# Driver_Morpheus_v4_0_PONTE_H.net
KiCad netlist of a schematic drawn in Altium Designer
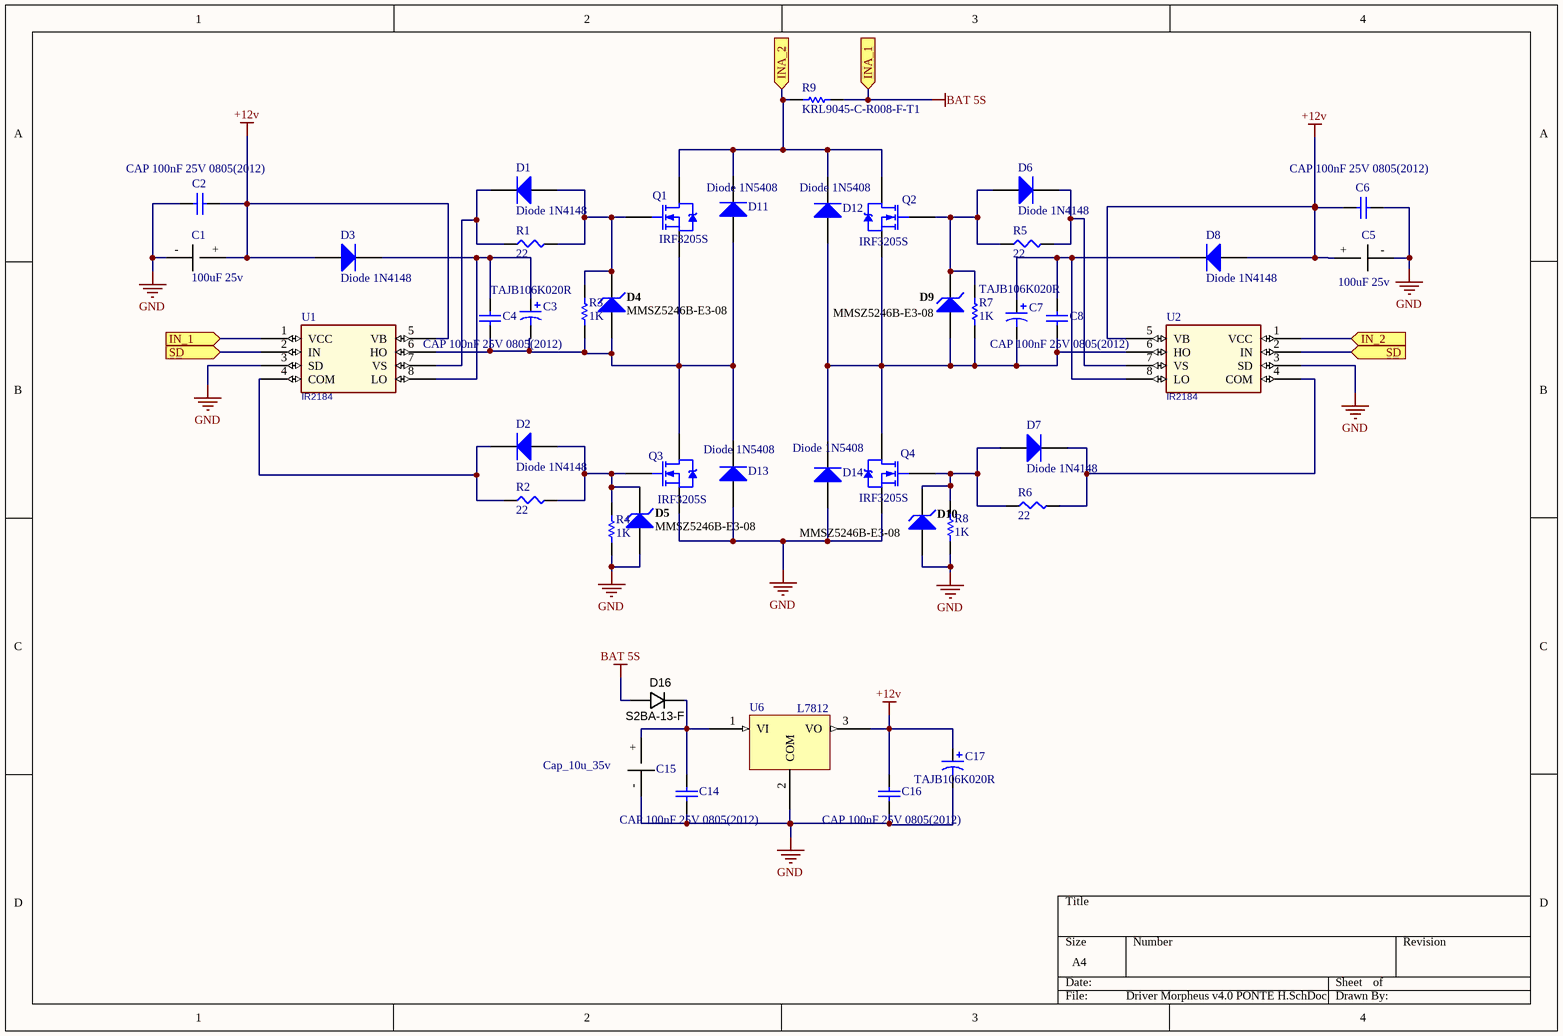
[diagram p0: Driver Morpheus v4.0 PONTE H.SchDoc]

(export (version "E")
  (design (tool "Eeschema 10.0.6"))
  (components
    (comp (ref "C1")
      (value "100uF 25v")
      (footprint "CAP_100u_25v_Tantalum")
      (description "Cap Tântalo")
      (libsource (lib "LibSanhaço2017") (part "Cap_100u_25v"))
    )
    (comp (ref "C2")
      (value "CAP 100nF 25V 0805(2012)")
      (footprint "CAPC0805(2012)145_M")
      (description "CAP 100nF 25V ±5% 0805 (2012 Metric) Thickness 1.45mm SMD")
      (fields (field (name "TOLERANCE") "Â±5%"))
      (libsource (lib "Altium Content Vault") (part "CAP"))
    )
    (comp (ref "C3")
      (value "TAJB106K020R")
      (footprint "AVX-CAPC3528_V")
      (description "Capacitor, Tantalum, 10uF 10% 20V MCCT-B (3528)")
      (fields (field (name "MANUFACTURER") "AVX") (field (name "TOLERANCE") "10%"))
      (libsource (lib "Altium Content Vault") (part "AVX-CAP-P-2"))
    )
    (comp (ref "C4")
      (value "CAP 100nF 25V 0805(2012)")
      (footprint "CAPC0805(2012)145_M")
      (description "CAP 100nF 25V ±5% 0805 (2012 Metric) Thickness 1.45mm SMD")
      (fields (field (name "TOLERANCE") "Â±5%"))
      (libsource (lib "Altium Content Vault") (part "CAP"))
    )
    (comp (ref "C5")
      (value "100uF 25v")
      (footprint "CAP_100u_25v_Tantalum")
      (description "Cap Tântalo")
      (libsource (lib "LibSanhaço2017") (part "Cap_100u_25v"))
    )
    (comp (ref "C6")
      (value "CAP 100nF 25V 0805(2012)")
      (footprint "CAPC0805(2012)145_M")
      (description "CAP 100nF 25V ±5% 0805 (2012 Metric) Thickness 1.45mm SMD")
      (fields (field (name "TOLERANCE") "Â±5%"))
      (libsource (lib "Altium Content Vault") (part "CAP"))
    )
    (comp (ref "C7")
      (value "TAJB106K020R")
      (footprint "AVX-CAPC3528_V")
      (description "Capacitor, Tantalum, 10uF 10% 20V MCCT-B (3528)")
      (fields (field (name "MANUFACTURER") "AVX") (field (name "TOLERANCE") "10%"))
      (libsource (lib "Altium Content Vault") (part "AVX-CAP-P-2"))
    )
    (comp (ref "C8")
      (value "CAP 100nF 25V 0805(2012)")
      (footprint "CAPC0805(2012)145_M")
      (description "CAP 100nF 25V ±5% 0805 (2012 Metric) Thickness 1.45mm SMD")
      (fields (field (name "TOLERANCE") "Â±5%"))
      (libsource (lib "Altium Content Vault") (part "CAP"))
    )
    (comp (ref "C14")
      (value "CAP 100nF 25V 0805(2012)")
      (footprint "CAPC0805(2012)145_M")
      (description "CAP 100nF 25V ±5% 0805 (2012 Metric) Thickness 1.45mm SMD")
      (fields (field (name "TOLERANCE") "Â±5%"))
      (libsource (lib "Altium Content Vault") (part "CAP"))
    )
    (comp (ref "C15")
      (value "Cap_10u_35v")
      (footprint "CAP_100u_25v_Tantalum")
      (libsource (lib "LibSanhaço2017") (part "Cap_10u_35v"))
    )
    (comp (ref "C16")
      (value "CAP 100nF 25V 0805(2012)")
      (footprint "CAPC0805(2012)145_M")
      (description "CAP 100nF 25V ±5% 0805 (2012 Metric) Thickness 1.45mm SMD")
      (fields (field (name "TOLERANCE") "Â±5%"))
      (libsource (lib "Altium Content Vault") (part "CAP"))
    )
    (comp (ref "C17")
      (value "TAJB106K020R")
      (footprint "AVX-CAPC3528_V")
      (description "Capacitor, Tantalum, 10uF 10% 20V MCCT-B (3528)")
      (fields (field (name "MANUFACTURER") "AVX") (field (name "TOLERANCE") "10%"))
      (libsource (lib "Altium Content Vault") (part "AVX-CAP-P-2"))
    )
    (comp (ref "D1")
      (value "Diode 1N4148")
      (footprint "SOD123")
      (description "High Conductance Fast Diode")
      (fields (field (name "PUBLISHER") "Altium Limited"))
      (libsource (lib "Miscellaneous Devices") (part "Diode 1N4148"))
    )
    (comp (ref "D2")
      (value "Diode 1N4148")
      (footprint "SOD123")
      (description "High Conductance Fast Diode")
      (fields (field (name "PUBLISHER") "Altium Limited"))
      (libsource (lib "Miscellaneous Devices") (part "Diode 1N4148"))
    )
    (comp (ref "D3")
      (value "Diode 1N4148")
      (footprint "SOD123")
      (description "High Conductance Fast Diode")
      (fields (field (name "PUBLISHER") "Altium Limited"))
      (libsource (lib "Miscellaneous Devices") (part "Diode 1N4148"))
    )
    (comp (ref "D4")
      (value "MMSZ5246B-E3-08")
      (footprint "VISH-SOD-123-2_V")
      (description "Small Signal Zener Diode, 16 V +/- 5%, -55 to 155 degC, 2-Pin SOD-123, RoHS, Tape and Reel")
      (fields (field (name "MANUFACTURER") "Vishay Semiconductor") (field (name "TOLERANCE") "+/- 5%"))
      (libsource (lib "Altium Content Vault") (part "VISH-DZEN_A1K2-2"))
    )
    (comp (ref "D5")
      (value "MMSZ5246B-E3-08")
      (footprint "VISH-SOD-123-2_V")
      (description "Small Signal Zener Diode, 16 V +/- 5%, -55 to 155 degC, 2-Pin SOD-123, RoHS, Tape and Reel")
      (fields (field (name "MANUFACTURER") "Vishay Semiconductor") (field (name "TOLERANCE") "+/- 5%"))
      (libsource (lib "Altium Content Vault") (part "VISH-DZEN_A1K2-2"))
    )
    (comp (ref "D6")
      (value "Diode 1N4148")
      (footprint "SOD123")
      (description "High Conductance Fast Diode")
      (fields (field (name "PUBLISHER") "Altium Limited"))
      (libsource (lib "Miscellaneous Devices") (part "Diode 1N4148"))
    )
    (comp (ref "D7")
      (value "Diode 1N4148")
      (footprint "SOD123")
      (description "High Conductance Fast Diode")
      (fields (field (name "PUBLISHER") "Altium Limited"))
      (libsource (lib "Miscellaneous Devices") (part "Diode 1N4148"))
    )
    (comp (ref "D8")
      (value "Diode 1N4148")
      (footprint "SOD123")
      (description "High Conductance Fast Diode")
      (fields (field (name "PUBLISHER") "Altium Limited"))
      (libsource (lib "Miscellaneous Devices") (part "Diode 1N4148"))
    )
    (comp (ref "D9")
      (value "MMSZ5246B-E3-08")
      (footprint "VISH-SOD-123-2_V")
      (description "Small Signal Zener Diode, 16 V +/- 5%, -55 to 155 degC, 2-Pin SOD-123, RoHS, Tape and Reel")
      (fields (field (name "MANUFACTURER") "Vishay Semiconductor") (field (name "TOLERANCE") "+/- 5%"))
      (libsource (lib "Altium Content Vault") (part "CMP-0931-00032-1"))
    )
    (comp (ref "D10")
      (value "MMSZ5246B-E3-08")
      (footprint "VISH-SOD-123-2_V")
      (description "Small Signal Zener Diode, 16 V +/- 5%, -55 to 155 degC, 2-Pin SOD-123, RoHS, Tape and Reel")
      (fields (field (name "MANUFACTURER") "Vishay Semiconductor") (field (name "TOLERANCE") "+/- 5%"))
      (libsource (lib "Altium Content Vault") (part "VISH-DZEN_A1K2-2"))
    )
    (comp (ref "D11")
      (value "Diode 1N5408")
      (footprint "DO-201AD")
      (description "3 Amp Medium Power Silicon Rectifier Diode")
      (fields (field (name "PUBLISHER") "Altium Limited"))
      (libsource (lib "Miscellaneous Devices") (part "Diode 1N5408"))
    )
    (comp (ref "D12")
      (value "Diode 1N5408")
      (footprint "DO-201AD")
      (description "3 Amp Medium Power Silicon Rectifier Diode")
      (fields (field (name "PUBLISHER") "Altium Limited"))
      (libsource (lib "Miscellaneous Devices") (part "Diode 1N5408"))
    )
    (comp (ref "D13")
      (value "Diode 1N5408")
      (footprint "DO-201AD")
      (description "3 Amp Medium Power Silicon Rectifier Diode")
      (fields (field (name "PUBLISHER") "Altium Limited"))
      (libsource (lib "Miscellaneous Devices") (part "Diode 1N5408"))
    )
    (comp (ref "D14")
      (value "Diode 1N5408")
      (footprint "DO-201AD")
      (description "3 Amp Medium Power Silicon Rectifier Diode")
      (fields (field (name "PUBLISHER") "Altium Limited"))
      (libsource (lib "Miscellaneous Devices") (part "Diode 1N5408"))
    )
    (comp (ref "D16")
      (value "100V; 1.5A")
      (footprint "DO-214AC")
      (description "Diode SMD 100V 1.5A SMA")
      (fields (field (name "MANUFACTURER PART NUMBER 1") "S2BA-13-F"))
      (libsource (lib "PBL - Diodes") (part "DIODE_100V_1.5A_SMA"))
    )
    (comp (ref "Q1")
      (value "IRF3205S")
      (footprint "D2PAK_N")
      (description "HEXFET Power MOSFET")
      (fields (field (name "PUBLISHER") "Altium Limited"))
      (libsource (lib "IR Discrete MOSFET - Power") (part "IRF3205S"))
    )
    (comp (ref "Q2")
      (value "IRF3205S")
      (footprint "D2PAK_N")
      (description "HEXFET Power MOSFET")
      (fields (field (name "PUBLISHER") "Altium Limited"))
      (libsource (lib "IR Discrete MOSFET - Power") (part "IRF3205S"))
    )
    (comp (ref "Q3")
      (value "IRF3205S")
      (footprint "D2PAK_N")
      (description "HEXFET Power MOSFET")
      (fields (field (name "PUBLISHER") "Altium Limited"))
      (libsource (lib "IR Discrete MOSFET - Power") (part "IRF3205S"))
    )
    (comp (ref "Q4")
      (value "IRF3205S")
      (footprint "D2PAK_N")
      (description "HEXFET Power MOSFET")
      (fields (field (name "PUBLISHER") "Altium Limited"))
      (libsource (lib "IR Discrete MOSFET - Power") (part "IRF3205S"))
    )
    (comp (ref "R1")
      (value "22")
      (footprint "SMD-0603-RES")
      (description "RES SMD 22 OHM 1% 1/10W 0603")
      (fields
        (field (name "PART NUMBER") "ERJ-3EKF22R0V")
        (field (name "DIGI-KEY PART NUMBER") "P22.0HCT-ND")
      )
      (libsource (lib "Panasonic_ERJ_0603") (part "ERJ-3EKF22R0V"))
    )
    (comp (ref "R2")
      (value "22")
      (footprint "SMD-0603-RES")
      (description "RES SMD 22 OHM 1% 1/10W 0603")
      (fields
        (field (name "PART NUMBER") "ERJ-3EKF22R0V")
        (field (name "DIGI-KEY PART NUMBER") "P22.0HCT-ND")
      )
      (libsource (lib "Panasonic_ERJ_0603") (part "ERJ-3EKF22R0V"))
    )
    (comp (ref "R3")
      (value "1K")
      (footprint "RES-0402")
      (description "RES SMD 1K OHM 5% 1/16W 0402")
      (fields (field (name "Comment") "RC0402JR-071KL"))
      (libsource (lib "Schlib1") (part "RES 1K 0402"))
    )
    (comp (ref "R4")
      (value "1K")
      (footprint "RES-0402")
      (description "RES SMD 1K OHM 5% 1/16W 0402")
      (fields (field (name "Comment") "RC0402JR-071KL"))
      (libsource (lib "Schlib1") (part "RES 1K 0402"))
    )
    (comp (ref "R5")
      (value "22")
      (footprint "SMD-0603-RES")
      (description "RES SMD 22 OHM 1% 1/10W 0603")
      (fields
        (field (name "PART NUMBER") "ERJ-3EKF22R0V")
        (field (name "DIGI-KEY PART NUMBER") "P22.0HCT-ND")
      )
      (libsource (lib "Panasonic_ERJ_0603") (part "ERJ-3EKF22R0V"))
    )
    (comp (ref "R6")
      (value "22")
      (footprint "SMD-0603-RES")
      (description "RES SMD 22 OHM 1% 1/10W 0603")
      (fields
        (field (name "PART NUMBER") "ERJ-3EKF22R0V")
        (field (name "DIGI-KEY PART NUMBER") "P22.0HCT-ND")
      )
      (libsource (lib "Panasonic_ERJ_0603") (part "ERJ-3EKF22R0V"))
    )
    (comp (ref "R7")
      (value "1K")
      (footprint "RES-0402")
      (description "RES SMD 1K OHM 5% 1/16W 0402")
      (fields (field (name "Comment") "RC0402JR-071KL"))
      (libsource (lib "Schlib1") (part "RES 1K 0402"))
    )
    (comp (ref "R8")
      (value "1K")
      (footprint "RES-0402")
      (description "RES SMD 1K OHM 5% 1/16W 0402")
      (fields (field (name "Comment") "RC0402JR-071KL"))
      (libsource (lib "Schlib1") (part "RES 1K 0402"))
    )
    (comp (ref "R9")
      (value "KRL9045-C-R008-F-T1")
      (footprint "8m OHM 4W")
      (description "Chip Resistor, 0.008 Ohm, +/- 1%, 4 W")
      (fields (field (name "TOLERANCE") "1%") (field (name "PARTNUMBER") "WSLP12061L000FEA"))
      (libsource (lib "altium-import") (part "root_2_RES-2_"))
    )
    (comp (ref "U1")
      (value "IR2184")
      (footprint "SOIC127P600X175-8AN")
      (libsource (lib "IR2184") (part "IR2184"))
    )
    (comp (ref "U2")
      (value "IR2184")
      (footprint "SOIC127P600X175-8AN")
      (libsource (lib "") (part "IR2184_1"))
    )
    (comp (ref "U6") (value "L7812") (footprint "D2PAK-3") (libsource (lib "78XX") (part "LM7812")))
  )
  (nets
    (net (code "1") (name "+12v") (class "Default")
      (node (ref "C1") (pin "+") (pintype "passive"))
      (node (ref "C16") (pin "2") (pinfunction "2_2") (pintype "passive"))
      (node (ref "C17") (pin "1") (pinfunction "1_1") (pintype "passive"))
      (node (ref "C2") (pin "2") (pinfunction "2_2") (pintype "passive"))
      (node (ref "C5") (pin "+") (pintype "passive"))
      (node (ref "C6") (pin "2") (pinfunction "2_2") (pintype "passive"))
      (node (ref "D3") (pin "1") (pinfunction "A_1") (pintype "passive"))
      (node (ref "D8") (pin "1") (pinfunction "A_1") (pintype "passive"))
      (node (ref "U1") (pin "5") (pinfunction "VB_5") (pintype "bidirectional"))
      (node (ref "U2") (pin "5") (pinfunction "VB_5") (pintype "bidirectional"))
      (node (ref "U6") (pin "3") (pinfunction "VO_3") (pintype "output"))
    )
    (net (code "2") (name "/INA_2") (class "Default")
      (node (ref "D11") (pin "2") (pinfunction "K_2") (pintype "passive"))
      (node (ref "D12") (pin "2") (pinfunction "K_2") (pintype "passive"))
      (node (ref "Q1") (pin "2") (pinfunction "D_2") (pintype "passive"))
      (node (ref "Q2") (pin "2") (pinfunction "D_2") (pintype "passive"))
      (node (ref "R9") (pin "2") (pinfunction "2_2") (pintype "passive"))
    )
    (net (code "3") (name "/IN_1") (class "Default")
      (node (ref "U1") (pin "1") (pinfunction "VCC_1") (pintype "bidirectional"))
    )
    (net (code "4") (name "/IN_2") (class "Default")
      (node (ref "U2") (pin "1") (pinfunction "VCC_1") (pintype "bidirectional"))
    )
    (net (code "5") (name "/SD") (class "Default")
      (node (ref "U1") (pin "2") (pinfunction "IN_2") (pintype "bidirectional"))
      (node (ref "U2") (pin "2") (pinfunction "IN_2") (pintype "bidirectional"))
    )
    (net (code "6") (name "BAT 5S") (class "Default")
      (node (ref "D16") (pin "A") (pinfunction "A_A") (pintype "passive"))
      (node (ref "R9") (pin "1") (pinfunction "1_1") (pintype "passive"))
    )
    (net (code "7") (name "GND") (class "Default")
      (node (ref "C1") (pin "-") (pintype "passive"))
      (node (ref "C14") (pin "1") (pinfunction "1_1") (pintype "passive"))
      (node (ref "C15") (pin "-") (pintype "passive"))
      (node (ref "C16") (pin "1") (pinfunction "1_1") (pintype "passive"))
      (node (ref "C17") (pin "2") (pinfunction "2_2") (pintype "passive"))
      (node (ref "C2") (pin "1") (pinfunction "1_1") (pintype "passive"))
      (node (ref "C5") (pin "-") (pintype "passive"))
      (node (ref "C6") (pin "1") (pinfunction "1_1") (pintype "passive"))
      (node (ref "D10") (pin "1") (pinfunction "A_1") (pintype "passive"))
      (node (ref "D13") (pin "1") (pinfunction "A_1") (pintype "passive"))
      (node (ref "D14") (pin "1") (pinfunction "A_1") (pintype "passive"))
      (node (ref "D5") (pin "1") (pinfunction "A_1") (pintype "passive"))
      (node (ref "Q3") (pin "3") (pinfunction "S_3") (pintype "passive"))
      (node (ref "Q4") (pin "3") (pinfunction "S_3") (pintype "passive"))
      (node (ref "R4") (pin "1") (pinfunction "1_1") (pintype "passive"))
      (node (ref "R8") (pin "1") (pinfunction "1_1") (pintype "passive"))
      (node (ref "U1") (pin "3") (pinfunction "SD_3") (pintype "bidirectional"))
      (node (ref "U2") (pin "3") (pinfunction "SD_3") (pintype "bidirectional"))
      (node (ref "U6") (pin "2") (pinfunction "COM_2") (pintype "power_in"))
    )
    (net (code "8") (name "Net-(D1-A)") (class "Default")
      (node (ref "D1") (pin "1") (pinfunction "A_1") (pintype "passive"))
      (node (ref "D4") (pin "2") (pinfunction "K_2") (pintype "passive"))
      (node (ref "Q1") (pin "1") (pinfunction "G_1") (pintype "passive"))
      (node (ref "R1") (pin "2") (pinfunction "2_2") (pintype "passive"))
      (node (ref "R3") (pin "2") (pinfunction "2_2") (pintype "passive"))
    )
    (net (code "9") (name "Net-(D1-K)") (class "Default")
      (node (ref "D1") (pin "2") (pinfunction "K_2") (pintype "passive"))
      (node (ref "R1") (pin "1") (pinfunction "1_1") (pintype "passive"))
      (node (ref "U1") (pin "7") (pinfunction "VS_7") (pintype "bidirectional"))
    )
    (net (code "10") (name "Net-(D2-A)") (class "Default")
      (node (ref "D2") (pin "1") (pinfunction "A_1") (pintype "passive"))
      (node (ref "D5") (pin "2") (pinfunction "K_2") (pintype "passive"))
      (node (ref "Q3") (pin "1") (pinfunction "G_1") (pintype "passive"))
      (node (ref "R2") (pin "2") (pinfunction "2_2") (pintype "passive"))
      (node (ref "R4") (pin "2") (pinfunction "2_2") (pintype "passive"))
    )
    (net (code "11") (name "Net-(D2-K)") (class "Default")
      (node (ref "D2") (pin "2") (pinfunction "K_2") (pintype "passive"))
      (node (ref "R2") (pin "1") (pinfunction "1_1") (pintype "passive"))
      (node (ref "U1") (pin "4") (pinfunction "COM_4") (pintype "bidirectional"))
    )
    (net (code "12") (name "Net-(D3-K)") (class "Default")
      (node (ref "C3") (pin "1") (pinfunction "1_1") (pintype "passive"))
      (node (ref "C4") (pin "2") (pinfunction "2_2") (pintype "passive"))
      (node (ref "D3") (pin "2") (pinfunction "K_2") (pintype "passive"))
      (node (ref "U1") (pin "8") (pinfunction "LO_8") (pintype "bidirectional"))
    )
    (net (code "13") (name "Net-(D6-A)") (class "Default")
      (node (ref "D6") (pin "1") (pinfunction "A_1") (pintype "passive"))
      (node (ref "D9") (pin "2") (pinfunction "K_2") (pintype "passive"))
      (node (ref "Q2") (pin "1") (pinfunction "G_1") (pintype "passive"))
      (node (ref "R5") (pin "1") (pinfunction "1_1") (pintype "passive"))
      (node (ref "R7") (pin "2") (pinfunction "2_2") (pintype "passive"))
    )
    (net (code "14") (name "Net-(D6-K)") (class "Default")
      (node (ref "D6") (pin "2") (pinfunction "K_2") (pintype "passive"))
      (node (ref "R5") (pin "2") (pinfunction "2_2") (pintype "passive"))
      (node (ref "U2") (pin "7") (pinfunction "VS_7") (pintype "bidirectional"))
    )
    (net (code "15") (name "Net-(D7-K)") (class "Default")
      (node (ref "D7") (pin "2") (pinfunction "K_2") (pintype "passive"))
      (node (ref "R6") (pin "2") (pinfunction "2_2") (pintype "passive"))
      (node (ref "U2") (pin "4") (pinfunction "COM_4") (pintype "bidirectional"))
    )
    (net (code "16") (name "Net-(D8-K)") (class "Default")
      (node (ref "C7") (pin "1") (pinfunction "1_1") (pintype "passive"))
      (node (ref "C8") (pin "2") (pinfunction "2_2") (pintype "passive"))
      (node (ref "D8") (pin "2") (pinfunction "K_2") (pintype "passive"))
      (node (ref "U2") (pin "8") (pinfunction "LO_8") (pintype "bidirectional"))
    )
    (net (code "17") (name "Net-(D10-K)") (class "Default")
      (node (ref "D10") (pin "2") (pinfunction "K_2") (pintype "passive"))
      (node (ref "D7") (pin "1") (pinfunction "A_1") (pintype "passive"))
      (node (ref "Q4") (pin "1") (pinfunction "G_1") (pintype "passive"))
      (node (ref "R6") (pin "1") (pinfunction "1_1") (pintype "passive"))
      (node (ref "R8") (pin "2") (pinfunction "2_2") (pintype "passive"))
    )
    (net (code "18") (name "Net-(D11-A)") (class "Default")
      (node (ref "C3") (pin "2") (pinfunction "2_2") (pintype "passive"))
      (node (ref "C4") (pin "1") (pinfunction "1_1") (pintype "passive"))
      (node (ref "D11") (pin "1") (pinfunction "A_1") (pintype "passive"))
      (node (ref "D13") (pin "2") (pinfunction "K_2") (pintype "passive"))
      (node (ref "D4") (pin "1") (pinfunction "A_1") (pintype "passive"))
      (node (ref "Q1") (pin "3") (pinfunction "S_3") (pintype "passive"))
      (node (ref "Q3") (pin "2") (pinfunction "D_2") (pintype "passive"))
      (node (ref "R3") (pin "1") (pinfunction "1_1") (pintype "passive"))
      (node (ref "U1") (pin "6") (pinfunction "HO_6") (pintype "bidirectional"))
    )
    (net (code "19") (name "Net-(D12-A)") (class "Default")
      (node (ref "C7") (pin "2") (pinfunction "2_2") (pintype "passive"))
      (node (ref "C8") (pin "1") (pinfunction "1_1") (pintype "passive"))
      (node (ref "D12") (pin "1") (pinfunction "A_1") (pintype "passive"))
      (node (ref "D14") (pin "2") (pinfunction "K_2") (pintype "passive"))
      (node (ref "D9") (pin "1") (pinfunction "A_1") (pintype "passive"))
      (node (ref "Q2") (pin "3") (pinfunction "S_3") (pintype "passive"))
      (node (ref "Q4") (pin "2") (pinfunction "D_2") (pintype "passive"))
      (node (ref "R7") (pin "1") (pinfunction "1_1") (pintype "passive"))
      (node (ref "U2") (pin "6") (pinfunction "HO_6") (pintype "bidirectional"))
    )
    (net (code "20") (name "Net-(U6-VI)") (class "Default")
      (node (ref "C14") (pin "2") (pinfunction "2_2") (pintype "passive"))
      (node (ref "C15") (pin "+") (pintype "passive"))
      (node (ref "D16") (pin "K") (pinfunction "K_K") (pintype "passive"))
      (node (ref "U6") (pin "1") (pinfunction "VI_1") (pintype "input"))
    )
  )
)
